# Sheet1.net
KiCad netlist of a schematic drawn in Altium Designer
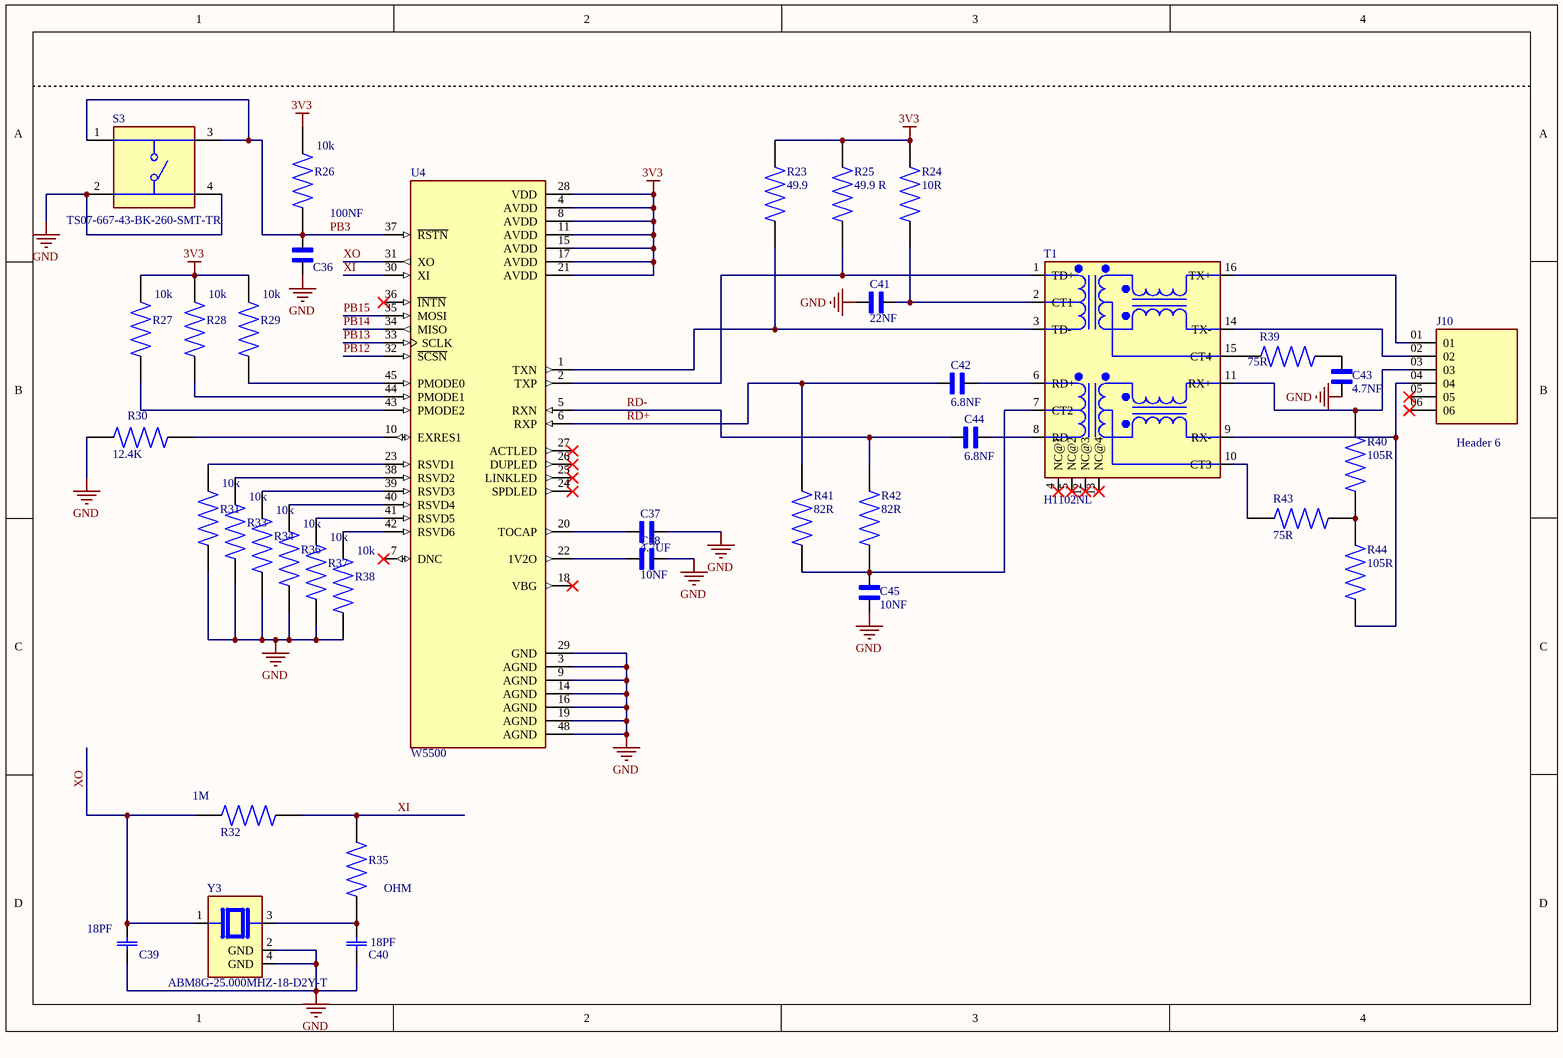
[diagram p0: Sheet1.SchDoc]

(export (version "E")
  (design (tool "Eeschema 10.0.6"))
  (components
    (comp (ref "C36")
      (value "100NF")
      (footprint "CAPC1608X90")
      (fields (field (name "MF") "KEMET") (field (name "MP") "C0603C104J3RACTU"))
      (libsource (lib "") (part "C0603C104J3RACTU_2"))
    )
    (comp (ref "C37")
      (value "4.7UF")
      (footprint "CAPC2012X135N")
      (description "2.2 ÂµF Â±10% 10V Ceramic Capacitor X7R 0805 (2012 Metric)")
      (fields (field (name "MF") "Samsung") (field (name "MP") "CL21B225KPFNNNG"))
      (libsource (lib "Accelo Integrated_Library") (part "CL21B225KPFNNNG"))
    )
    (comp (ref "C38")
      (value "10NF")
      (footprint "CAPC1608X90")
      (fields (field (name "MF") "KEMET") (field (name "MP") "C0603C104J3RACTU"))
      (libsource (lib "Accelo Integrated_Library") (part "C0603C104J3RACTU"))
    )
    (comp (ref "C39")
      (value "18PF")
      (footprint "CAPC1608X85N")
      (description "Capacitor Ceramic C0G 0603 50V 20pF ¦ KEMET C0603C200J5GACTU")
      (fields (field (name "MF") "KEMET") (field (name "MP") "C0603C200J5GACTU"))
      (libsource (lib "Accelo Integrated_Library") (part "C0603C200J5GACTU"))
    )
    (comp (ref "C40")
      (value "18PF")
      (footprint "CAPC1608X85N")
      (description "Capacitor Ceramic C0G 0603 50V 20pF ¦ KEMET C0603C200J5GACTU")
      (fields (field (name "MF") "KEMET") (field (name "MP") "C0603C200J5GACTU"))
      (libsource (lib "Accelo Integrated_Library") (part "C0603C200J5GACTU"))
    )
    (comp (ref "C41")
      (value "22NF")
      (footprint "CAPC1608X90")
      (fields (field (name "MF") "KEMET") (field (name "MP") "C0603C104J3RACTU"))
      (libsource (lib "Accelo Integrated_Library") (part "C0603C104J3RACTU"))
    )
    (comp (ref "C42")
      (value "6.8NF")
      (footprint "CAPC1608X90")
      (fields (field (name "MF") "KEMET") (field (name "MP") "C0603C104J3RACTU"))
      (libsource (lib "Accelo Integrated_Library") (part "C0603C104J3RACTU"))
    )
    (comp (ref "C43")
      (value "4.7NF")
      (footprint "CAPC1608X90")
      (fields (field (name "MF") "KEMET") (field (name "MP") "C0603C104J3RACTU"))
      (libsource (lib "") (part "C0603C104J3RACTU_1"))
    )
    (comp (ref "C44")
      (value "6.8NF")
      (footprint "CAPC1608X90")
      (fields (field (name "MF") "KEMET") (field (name "MP") "C0603C104J3RACTU"))
      (libsource (lib "Accelo Integrated_Library") (part "C0603C104J3RACTU"))
    )
    (comp (ref "C45")
      (value "10NF")
      (footprint "CAPC1608X90")
      (fields (field (name "MF") "KEMET") (field (name "MP") "C0603C104J3RACTU"))
      (libsource (lib "") (part "C0603C104J3RACTU_1"))
    )
    (comp (ref "J10")
      (value "Header 6")
      (footprint "SAMTEC_MTLW-106-06-G-S-180")
      (fields (field (name "MP") "MTLW-106-06-G-S-180"))
      (libsource (lib "MTLW-106-06-G-S-180") (part "MTLW-106-06-G-S-180"))
    )
    (comp (ref "R23")
      (value "49.9")
      (footprint "RESC3116X65N")
      (description "0 Ohms Jumper Chip Resistor 1206 (3216 Metric) Automotive AEC-Q200 Thick Film")
      (fields (field (name "MF") "Yageo") (field (name "MP") "AC1206FR-070RL"))
      (libsource (lib "Accelo Integrated_Library") (part "AC1206FR-070RL"))
    )
    (comp (ref "R24")
      (value "10R")
      (footprint "RESC3116X65N")
      (description "0 Ohms Jumper Chip Resistor 1206 (3216 Metric) Automotive AEC-Q200 Thick Film")
      (fields (field (name "MF") "Yageo") (field (name "MP") "AC1206FR-070RL"))
      (libsource (lib "Accelo Integrated_Library") (part "AC1206FR-070RL"))
    )
    (comp (ref "R25")
      (value "49.9 R")
      (footprint "RESC3116X65N")
      (description "0 Ohms Jumper Chip Resistor 1206 (3216 Metric) Automotive AEC-Q200 Thick Film")
      (fields (field (name "MF") "Yageo") (field (name "MP") "AC1206FR-070RL"))
      (libsource (lib "Accelo Integrated_Library") (part "AC1206FR-070RL"))
    )
    (comp (ref "R26")
      (value "10k")
      (footprint "RESC3116X65N")
      (description "0 Ohms Jumper Chip Resistor 1206 (3216 Metric) Automotive AEC-Q200 Thick Film")
      (fields (field (name "MF") "Yageo") (field (name "MP") "AC1206FR-070RL"))
      (libsource (lib "Accelo Integrated_Library") (part "AC1206FR-070RL"))
    )
    (comp (ref "R27")
      (value "10k")
      (footprint "RESC3116X65N")
      (description "0 Ohms Jumper Chip Resistor 1206 (3216 Metric) Automotive AEC-Q200 Thick Film")
      (fields (field (name "MF") "Yageo") (field (name "MP") "AC1206FR-070RL"))
      (libsource (lib "Accelo Integrated_Library") (part "AC1206FR-070RL"))
    )
    (comp (ref "R28")
      (value "10k")
      (footprint "RESC3116X65N")
      (description "0 Ohms Jumper Chip Resistor 1206 (3216 Metric) Automotive AEC-Q200 Thick Film")
      (fields (field (name "MF") "Yageo") (field (name "MP") "AC1206FR-070RL"))
      (libsource (lib "Accelo Integrated_Library") (part "AC1206FR-070RL"))
    )
    (comp (ref "R29")
      (value "10k")
      (footprint "RESC3116X65N")
      (description "0 Ohms Jumper Chip Resistor 1206 (3216 Metric) Automotive AEC-Q200 Thick Film")
      (fields (field (name "MF") "Yageo") (field (name "MP") "AC1206FR-070RL"))
      (libsource (lib "Accelo Integrated_Library") (part "AC1206FR-070RL"))
    )
    (comp (ref "R30")
      (value "12.4K")
      (footprint "RESC3116X65N")
      (description "0 Ohms Jumper Chip Resistor 1206 (3216 Metric) Automotive AEC-Q200 Thick Film")
      (fields (field (name "MF") "Yageo") (field (name "MP") "AC1206FR-070RL"))
      (libsource (lib "Accelo Integrated_Library") (part "AC1206FR-070RL"))
    )
    (comp (ref "R31")
      (value "10k")
      (footprint "RESC3116X65N")
      (description "0 Ohms Jumper Chip Resistor 1206 (3216 Metric) Automotive AEC-Q200 Thick Film")
      (fields (field (name "MF") "Yageo") (field (name "MP") "AC1206FR-070RL"))
      (libsource (lib "Accelo Integrated_Library") (part "AC1206FR-070RL"))
    )
    (comp (ref "R32")
      (value "1M")
      (footprint "RESC3116X65N")
      (description "0 Ohms Jumper Chip Resistor 1206 (3216 Metric) Automotive AEC-Q200 Thick Film")
      (fields (field (name "MF") "Yageo") (field (name "MP") "AC1206FR-070RL"))
      (libsource (lib "Accelo Integrated_Library") (part "AC1206FR-070RL"))
    )
    (comp (ref "R33")
      (value "10k")
      (footprint "RESC3116X65N")
      (description "0 Ohms Jumper Chip Resistor 1206 (3216 Metric) Automotive AEC-Q200 Thick Film")
      (fields (field (name "MF") "Yageo") (field (name "MP") "AC1206FR-070RL"))
      (libsource (lib "Accelo Integrated_Library") (part "AC1206FR-070RL"))
    )
    (comp (ref "R34")
      (value "10k")
      (footprint "RESC3116X65N")
      (description "0 Ohms Jumper Chip Resistor 1206 (3216 Metric) Automotive AEC-Q200 Thick Film")
      (fields (field (name "MF") "Yageo") (field (name "MP") "AC1206FR-070RL"))
      (libsource (lib "Accelo Integrated_Library") (part "AC1206FR-070RL"))
    )
    (comp (ref "R35")
      (value "OHM")
      (footprint "RESC3116X65N")
      (description "0 Ohms Jumper Chip Resistor 1206 (3216 Metric) Automotive AEC-Q200 Thick Film")
      (fields (field (name "MF") "Yageo") (field (name "MP") "AC1206FR-070RL"))
      (libsource (lib "Accelo Integrated_Library") (part "AC1206FR-070RL"))
    )
    (comp (ref "R36")
      (value "10k")
      (footprint "RESC3116X65N")
      (description "0 Ohms Jumper Chip Resistor 1206 (3216 Metric) Automotive AEC-Q200 Thick Film")
      (fields (field (name "MF") "Yageo") (field (name "MP") "AC1206FR-070RL"))
      (libsource (lib "Accelo Integrated_Library") (part "AC1206FR-070RL"))
    )
    (comp (ref "R37")
      (value "10k")
      (footprint "RESC3116X65N")
      (description "0 Ohms Jumper Chip Resistor 1206 (3216 Metric) Automotive AEC-Q200 Thick Film")
      (fields (field (name "MF") "Yageo") (field (name "MP") "AC1206FR-070RL"))
      (libsource (lib "Accelo Integrated_Library") (part "AC1206FR-070RL"))
    )
    (comp (ref "R38")
      (value "10k")
      (footprint "RESC3116X65N")
      (description "0 Ohms Jumper Chip Resistor 1206 (3216 Metric) Automotive AEC-Q200 Thick Film")
      (fields (field (name "MF") "Yageo") (field (name "MP") "AC1206FR-070RL"))
      (libsource (lib "Accelo Integrated_Library") (part "AC1206FR-070RL"))
    )
    (comp (ref "R39")
      (value "75R")
      (footprint "RESC3116X65N")
      (description "0 Ohms Jumper Chip Resistor 1206 (3216 Metric) Automotive AEC-Q200 Thick Film")
      (fields (field (name "MF") "Yageo") (field (name "MP") "AC1206FR-070RL"))
      (libsource (lib "Accelo Integrated_Library") (part "AC1206FR-070RL"))
    )
    (comp (ref "R40")
      (value "105R")
      (footprint "RESC3116X65N")
      (description "0 Ohms Jumper Chip Resistor 1206 (3216 Metric) Automotive AEC-Q200 Thick Film")
      (fields (field (name "MF") "Yageo") (field (name "MP") "AC1206FR-070RL"))
      (libsource (lib "Accelo Integrated_Library") (part "AC1206FR-070RL"))
    )
    (comp (ref "R41")
      (value "82R")
      (footprint "RESC3116X65N")
      (description "0 Ohms Jumper Chip Resistor 1206 (3216 Metric) Automotive AEC-Q200 Thick Film")
      (fields (field (name "MF") "Yageo") (field (name "MP") "AC1206FR-070RL"))
      (libsource (lib "Accelo Integrated_Library") (part "AC1206FR-070RL"))
    )
    (comp (ref "R42")
      (value "82R")
      (footprint "RESC3116X65N")
      (description "0 Ohms Jumper Chip Resistor 1206 (3216 Metric) Automotive AEC-Q200 Thick Film")
      (fields (field (name "MF") "Yageo") (field (name "MP") "AC1206FR-070RL"))
      (libsource (lib "Accelo Integrated_Library") (part "AC1206FR-070RL"))
    )
    (comp (ref "R43")
      (value "75R")
      (footprint "RESC3116X65N")
      (description "0 Ohms Jumper Chip Resistor 1206 (3216 Metric) Automotive AEC-Q200 Thick Film")
      (fields (field (name "MF") "Yageo") (field (name "MP") "AC1206FR-070RL"))
      (libsource (lib "Accelo Integrated_Library") (part "AC1206FR-070RL"))
    )
    (comp (ref "R44")
      (value "105R")
      (footprint "RESC3116X65N")
      (description "0 Ohms Jumper Chip Resistor 1206 (3216 Metric) Automotive AEC-Q200 Thick Film")
      (fields (field (name "MF") "Yageo") (field (name "MP") "AC1206FR-070RL"))
      (libsource (lib "Accelo Integrated_Library") (part "AC1206FR-070RL"))
    )
    (comp (ref "S3")
      (value "TS07-667-43-BK-260-SMT-TR")
      (footprint "SW_TS07-667-43-BK-260-SMT-TR")
      (description "6 x 6.7 mm, 4.3 mm Actuator Height, 260 gf, Black, Surface Mount, SPST, Tactile Switch")
      (fields (field (name "MF") "Same Sky"))
      (libsource (lib "Accelo Integrated_Library") (part "TS07-667-43-BK-260-SMT-TR"))
    )
    (comp (ref "T1")
      (value "H1102NL")
      (footprint "H1102NL")
      (fields (field (name "MF") "Pulse"))
      (libsource (lib "H1102NL") (part "H1102NL"))
    )
    (comp (ref "U4")
      (value "W5500")
      (footprint "QFP50P900X900X160-48N")
      (description "Hardwired TCP/IP embedded Ethernet controller")
      (libsource (lib "W5500") (part "W5500"))
    )
    (comp (ref "Y3")
      (value "ABM8G-25.000MHZ-18-D2Y-T")
      (footprint "XTAL_ABM8G-25.000MHZ-18-D2Y-T")
      (description "25 MHz Â±20ppm Crystal 18pF 60 Ohms 4-SMD, No Lead")
      (fields (field (name "MF") "Abracon"))
      (libsource (lib "ABM8G-25.000MHZ-18-D2Y-T") (part "ABM8G-25.000MHZ-18-D2Y-T"))
    )
  )
  (nets
    (net (code "1") (name "/PB3") (class "Default")
      (node (ref "C36") (pin "2") (pinfunction "2_2") (pintype "passive"))
      (node (ref "R26") (pin "1") (pinfunction "1_1") (pintype "passive"))
      (node (ref "S3") (pin "1") (pinfunction "1_1") (pintype "passive"))
      (node (ref "S3") (pin "3") (pinfunction "3_3") (pintype "passive"))
      (node (ref "U4") (pin "37") (pinfunction "~{RSTN}_37") (pintype "input"))
    )
    (net (code "2") (name "/PB12") (class "Default")
      (node (ref "U4") (pin "32") (pinfunction "~{SCSN}_32") (pintype "input"))
    )
    (net (code "3") (name "/PB13") (class "Default")
      (node (ref "U4") (pin "33") (pinfunction "SCLK_33") (pintype "input"))
    )
    (net (code "4") (name "/PB14") (class "Default")
      (node (ref "U4") (pin "34") (pinfunction "MISO_34") (pintype "output"))
    )
    (net (code "5") (name "/PB15") (class "Default")
      (node (ref "U4") (pin "35") (pinfunction "MOSI_35") (pintype "input"))
    )
    (net (code "6") (name "/RD+") (class "Default")
      (node (ref "C42") (pin "2") (pinfunction "2_2") (pintype "passive"))
      (node (ref "R41") (pin "1") (pinfunction "1_1") (pintype "passive"))
      (node (ref "U4") (pin "6") (pinfunction "RXP_6") (pintype "input"))
    )
    (net (code "7") (name "/RD-") (class "Default")
      (node (ref "C44") (pin "2") (pinfunction "2_2") (pintype "passive"))
      (node (ref "R42") (pin "1") (pinfunction "1_1") (pintype "passive"))
      (node (ref "U4") (pin "5") (pinfunction "RXN_5") (pintype "input"))
    )
    (net (code "8") (name "/XI") (class "Default")
      (node (ref "R32") (pin "1") (pinfunction "1_1") (pintype "passive"))
      (node (ref "R35") (pin "2") (pinfunction "2_2") (pintype "passive"))
      (node (ref "U4") (pin "30") (pinfunction "XI_30") (pintype "input"))
    )
    (net (code "9") (name "/XO") (class "Default")
      (node (ref "C39") (pin "2") (pinfunction "C2_2") (pintype "passive"))
      (node (ref "R32") (pin "2") (pinfunction "2_2") (pintype "passive"))
      (node (ref "U4") (pin "31") (pinfunction "XO_31") (pintype "output"))
      (node (ref "Y3") (pin "1") (pinfunction "1_1") (pintype "passive"))
    )
    (net (code "10") (name "3V3") (class "Default")
      (node (ref "R23") (pin "1") (pinfunction "1_1") (pintype "passive"))
      (node (ref "R24") (pin "1") (pinfunction "1_1") (pintype "passive"))
      (node (ref "R25") (pin "1") (pinfunction "1_1") (pintype "passive"))
      (node (ref "R26") (pin "2") (pinfunction "2_2") (pintype "passive"))
      (node (ref "R27") (pin "2") (pinfunction "2_2") (pintype "passive"))
      (node (ref "R28") (pin "2") (pinfunction "2_2") (pintype "passive"))
      (node (ref "R29") (pin "2") (pinfunction "2_2") (pintype "passive"))
      (node (ref "U4") (pin "11") (pinfunction "AVDD_11") (pintype "power_in"))
      (node (ref "U4") (pin "15") (pinfunction "AVDD_15") (pintype "power_in"))
      (node (ref "U4") (pin "17") (pinfunction "AVDD_17") (pintype "power_in"))
      (node (ref "U4") (pin "21") (pinfunction "AVDD_21") (pintype "power_in"))
      (node (ref "U4") (pin "28") (pinfunction "VDD_28") (pintype "power_in"))
      (node (ref "U4") (pin "4") (pinfunction "AVDD_4") (pintype "power_in"))
      (node (ref "U4") (pin "8") (pinfunction "AVDD_8") (pintype "power_in"))
    )
    (net (code "11") (name "GND") (class "Default")
      (node (ref "C36") (pin "1") (pinfunction "1_1") (pintype "passive"))
      (node (ref "C37") (pin "2") (pinfunction "2_2") (pintype "passive"))
      (node (ref "C38") (pin "1") (pinfunction "1_1") (pintype "passive"))
      (node (ref "C39") (pin "1") (pinfunction "C1_1") (pintype "passive"))
      (node (ref "C40") (pin "1") (pinfunction "C1_1") (pintype "passive"))
      (node (ref "C41") (pin "2") (pinfunction "2_2") (pintype "passive"))
      (node (ref "C43") (pin "2") (pinfunction "2_2") (pintype "passive"))
      (node (ref "C45") (pin "2") (pinfunction "2_2") (pintype "passive"))
      (node (ref "R30") (pin "2") (pinfunction "2_2") (pintype "passive"))
      (node (ref "R31") (pin "1") (pinfunction "1_1") (pintype "passive"))
      (node (ref "R33") (pin "1") (pinfunction "1_1") (pintype "passive"))
      (node (ref "R34") (pin "1") (pinfunction "1_1") (pintype "passive"))
      (node (ref "R36") (pin "1") (pinfunction "1_1") (pintype "passive"))
      (node (ref "R37") (pin "1") (pinfunction "1_1") (pintype "passive"))
      (node (ref "R38") (pin "1") (pinfunction "1_1") (pintype "passive"))
      (node (ref "S3") (pin "2") (pinfunction "2_2") (pintype "passive"))
      (node (ref "S3") (pin "4") (pinfunction "4_4") (pintype "passive"))
      (node (ref "U4") (pin "14") (pinfunction "AGND_14") (pintype "power_in"))
      (node (ref "U4") (pin "16") (pinfunction "AGND_16") (pintype "power_in"))
      (node (ref "U4") (pin "19") (pinfunction "AGND_19") (pintype "power_in"))
      (node (ref "U4") (pin "29") (pinfunction "GND_29") (pintype "passive"))
      (node (ref "U4") (pin "3") (pinfunction "AGND_3") (pintype "power_in"))
      (node (ref "U4") (pin "48") (pinfunction "AGND_48") (pintype "power_in"))
      (node (ref "U4") (pin "9") (pinfunction "AGND_9") (pintype "power_in"))
      (node (ref "Y3") (pin "2") (pinfunction "GND_2") (pintype "power_in"))
      (node (ref "Y3") (pin "4") (pinfunction "GND_4") (pintype "power_in"))
    )
    (net (code "12") (name "Net-(C40-C2)") (class "Default")
      (node (ref "C40") (pin "2") (pinfunction "C2_2") (pintype "passive"))
      (node (ref "R35") (pin "1") (pinfunction "1_1") (pintype "passive"))
      (node (ref "Y3") (pin "3") (pinfunction "2_3") (pintype "passive"))
    )
    (net (code "13") (name "Net-(C43-Pad1)") (class "Default")
      (node (ref "C43") (pin "1") (pinfunction "1_1") (pintype "passive"))
      (node (ref "R39") (pin "2") (pinfunction "2_2") (pintype "passive"))
    )
    (net (code "14") (name "Net-(R40-Pad2)") (class "Default")
      (node (ref "R40") (pin "2") (pinfunction "2_2") (pintype "passive"))
      (node (ref "R43") (pin "2") (pinfunction "2_2") (pintype "passive"))
      (node (ref "R44") (pin "1") (pinfunction "1_1") (pintype "passive"))
    )
    (net (code "15") (name "Net-(T1-CT1)") (class "Default")
      (node (ref "C41") (pin "1") (pinfunction "1_1") (pintype "passive"))
      (node (ref "R24") (pin "2") (pinfunction "2_2") (pintype "passive"))
      (node (ref "T1") (pin "2") (pinfunction "CT1_2") (pintype "passive"))
    )
    (net (code "16") (name "Net-(T1-CT2)") (class "Default")
      (node (ref "C45") (pin "1") (pinfunction "1_1") (pintype "passive"))
      (node (ref "R41") (pin "2") (pinfunction "2_2") (pintype "passive"))
      (node (ref "R42") (pin "2") (pinfunction "2_2") (pintype "passive"))
      (node (ref "T1") (pin "7") (pinfunction "CT2_7") (pintype "passive"))
    )
    (net (code "17") (name "Net-(T1-CT3)") (class "Default")
      (node (ref "R43") (pin "1") (pinfunction "1_1") (pintype "passive"))
      (node (ref "T1") (pin "10") (pinfunction "CT3_10") (pintype "passive"))
    )
    (net (code "18") (name "Net-(T1-CT4)") (class "Default")
      (node (ref "R39") (pin "1") (pinfunction "1_1") (pintype "passive"))
      (node (ref "T1") (pin "15") (pinfunction "CT4_15") (pintype "passive"))
    )
    (net (code "19") (name "Net-(T1-RD+)") (class "Default")
      (node (ref "C42") (pin "1") (pinfunction "1_1") (pintype "passive"))
      (node (ref "T1") (pin "6") (pinfunction "RD+_6") (pintype "passive"))
    )
    (net (code "20") (name "Net-(T1-RD-)") (class "Default")
      (node (ref "C44") (pin "1") (pinfunction "1_1") (pintype "passive"))
      (node (ref "T1") (pin "8") (pinfunction "RD-_8") (pintype "passive"))
    )
    (net (code "21") (name "Net-(T1-RX+)") (class "Default")
      (node (ref "J10") (pin "03") (pinfunction "03_03") (pintype "passive"))
      (node (ref "R40") (pin "1") (pinfunction "1_1") (pintype "passive"))
      (node (ref "T1") (pin "11") (pinfunction "RX+_11") (pintype "passive"))
    )
    (net (code "22") (name "Net-(T1-RX-)") (class "Default")
      (node (ref "J10") (pin "04") (pinfunction "04_04") (pintype "passive"))
      (node (ref "R44") (pin "2") (pinfunction "2_2") (pintype "passive"))
      (node (ref "T1") (pin "9") (pinfunction "RX-_9") (pintype "passive"))
    )
    (net (code "23") (name "Net-(T1-TD+)") (class "Default")
      (node (ref "R25") (pin "2") (pinfunction "2_2") (pintype "passive"))
      (node (ref "T1") (pin "1") (pinfunction "TD+_1") (pintype "passive"))
      (node (ref "U4") (pin "2") (pinfunction "TXP_2") (pintype "output"))
    )
    (net (code "24") (name "Net-(T1-TD-)") (class "Default")
      (node (ref "R23") (pin "2") (pinfunction "2_2") (pintype "passive"))
      (node (ref "T1") (pin "3") (pinfunction "TD-_3") (pintype "passive"))
      (node (ref "U4") (pin "1") (pinfunction "TXN_1") (pintype "output"))
    )
    (net (code "25") (name "Net-(T1-TX+)") (class "Default")
      (node (ref "J10") (pin "01") (pinfunction "01_01") (pintype "passive"))
      (node (ref "T1") (pin "16") (pinfunction "TX+_16") (pintype "passive"))
    )
    (net (code "26") (name "Net-(T1-TX-)") (class "Default")
      (node (ref "J10") (pin "02") (pinfunction "02_02") (pintype "passive"))
      (node (ref "T1") (pin "14") (pinfunction "TX-_14") (pintype "passive"))
    )
    (net (code "27") (name "Net-(U4-1V2O)") (class "Default")
      (node (ref "C38") (pin "2") (pinfunction "2_2") (pintype "passive"))
      (node (ref "U4") (pin "22") (pinfunction "1V2O_22") (pintype "output"))
    )
    (net (code "28") (name "Net-(U4-EXRES1)") (class "Default")
      (node (ref "R30") (pin "1") (pinfunction "1_1") (pintype "passive"))
      (node (ref "U4") (pin "10") (pinfunction "EXRES1_10") (pintype "bidirectional"))
    )
    (net (code "29") (name "Net-(U4-PMODE0)") (class "Default")
      (node (ref "R29") (pin "1") (pinfunction "1_1") (pintype "passive"))
      (node (ref "U4") (pin "45") (pinfunction "PMODE0_45") (pintype "input"))
    )
    (net (code "30") (name "Net-(U4-PMODE1)") (class "Default")
      (node (ref "R28") (pin "1") (pinfunction "1_1") (pintype "passive"))
      (node (ref "U4") (pin "44") (pinfunction "PMODE1_44") (pintype "input"))
    )
    (net (code "31") (name "Net-(U4-PMODE2)") (class "Default")
      (node (ref "R27") (pin "1") (pinfunction "1_1") (pintype "passive"))
      (node (ref "U4") (pin "43") (pinfunction "PMODE2_43") (pintype "input"))
    )
    (net (code "32") (name "Net-(U4-RSVD1)") (class "Default")
      (node (ref "R31") (pin "2") (pinfunction "2_2") (pintype "passive"))
      (node (ref "U4") (pin "23") (pinfunction "RSVD1_23") (pintype "input"))
    )
    (net (code "33") (name "Net-(U4-RSVD2)") (class "Default")
      (node (ref "R33") (pin "2") (pinfunction "2_2") (pintype "passive"))
      (node (ref "U4") (pin "38") (pinfunction "RSVD2_38") (pintype "input"))
    )
    (net (code "34") (name "Net-(U4-RSVD3)") (class "Default")
      (node (ref "R34") (pin "2") (pinfunction "2_2") (pintype "passive"))
      (node (ref "U4") (pin "39") (pinfunction "RSVD3_39") (pintype "input"))
    )
    (net (code "35") (name "Net-(U4-RSVD4)") (class "Default")
      (node (ref "R36") (pin "2") (pinfunction "2_2") (pintype "passive"))
      (node (ref "U4") (pin "40") (pinfunction "RSVD4_40") (pintype "input"))
    )
    (net (code "36") (name "Net-(U4-RSVD5)") (class "Default")
      (node (ref "R37") (pin "2") (pinfunction "2_2") (pintype "passive"))
      (node (ref "U4") (pin "41") (pinfunction "RSVD5_41") (pintype "input"))
    )
    (net (code "37") (name "Net-(U4-RSVD6)") (class "Default")
      (node (ref "R38") (pin "2") (pinfunction "2_2") (pintype "passive"))
      (node (ref "U4") (pin "42") (pinfunction "RSVD6_42") (pintype "input"))
    )
    (net (code "38") (name "Net-(U4-TOCAP)") (class "Default")
      (node (ref "C37") (pin "1") (pinfunction "1_1") (pintype "passive"))
      (node (ref "U4") (pin "20") (pinfunction "TOCAP_20") (pintype "output"))
    )
    (net (code "39") (name "unconnected-(J10-Pad05)") (class "Default")
      (node (ref "J10") (pin "05") (pinfunction "05_05") (pintype "passive+no_connect"))
    )
    (net (code "40") (name "unconnected-(J10-Pad06)") (class "Default")
      (node (ref "J10") (pin "06") (pinfunction "06_06") (pintype "passive+no_connect"))
    )
    (net (code "41") (name "unconnected-(T1-NC@1-Pad4)") (class "Default")
      (node (ref "T1") (pin "4") (pinfunction "NC@1_4") (pintype "passive+no_connect"))
    )
    (net (code "42") (name "unconnected-(T1-NC@2-Pad5)") (class "Default")
      (node (ref "T1") (pin "5") (pinfunction "NC@2_5") (pintype "passive+no_connect"))
    )
    (net (code "43") (name "unconnected-(T1-NC@3-Pad12)") (class "Default")
      (node (ref "T1") (pin "12") (pinfunction "NC@3_12") (pintype "passive+no_connect"))
    )
    (net (code "44") (name "unconnected-(T1-NC@4-Pad13)") (class "Default")
      (node (ref "T1") (pin "13") (pinfunction "NC@4_13") (pintype "passive+no_connect"))
    )
    (net (code "45") (name "unconnected-(U4-ACTLED-Pad27)") (class "Default")
      (node (ref "U4") (pin "27") (pinfunction "ACTLED_27") (pintype "output+no_connect"))
    )
    (net (code "46") (name "unconnected-(U4-DNC-Pad7)") (class "Default")
      (node (ref "U4") (pin "7") (pinfunction "DNC_7") (pintype "bidirectional+no_connect"))
    )
    (net (code "47") (name "unconnected-(U4-DUPLED-Pad26)") (class "Default")
      (node (ref "U4") (pin "26") (pinfunction "DUPLED_26") (pintype "output+no_connect"))
    )
    (net (code "48") (name "unconnected-(U4-LINKLED-Pad25)") (class "Default")
      (node (ref "U4") (pin "25") (pinfunction "LINKLED_25") (pintype "output+no_connect"))
    )
    (net (code "49") (name "unconnected-(U4-SPDLED-Pad24)") (class "Default")
      (node (ref "U4") (pin "24") (pinfunction "SPDLED_24") (pintype "output+no_connect"))
    )
    (net (code "50") (name "unconnected-(U4-VBG-Pad18)") (class "Default")
      (node (ref "U4") (pin "18") (pinfunction "VBG_18") (pintype "output+no_connect"))
    )
    (net (code "51") (name "unconnected-(U4-~{INTN}-Pad36)") (class "Default")
      (node (ref "U4") (pin "36") (pinfunction "~{INTN}_36") (pintype "input+no_connect"))
    )
  )
)
